# 20190314.net
KiCad netlist of a schematic drawn in EAGLE
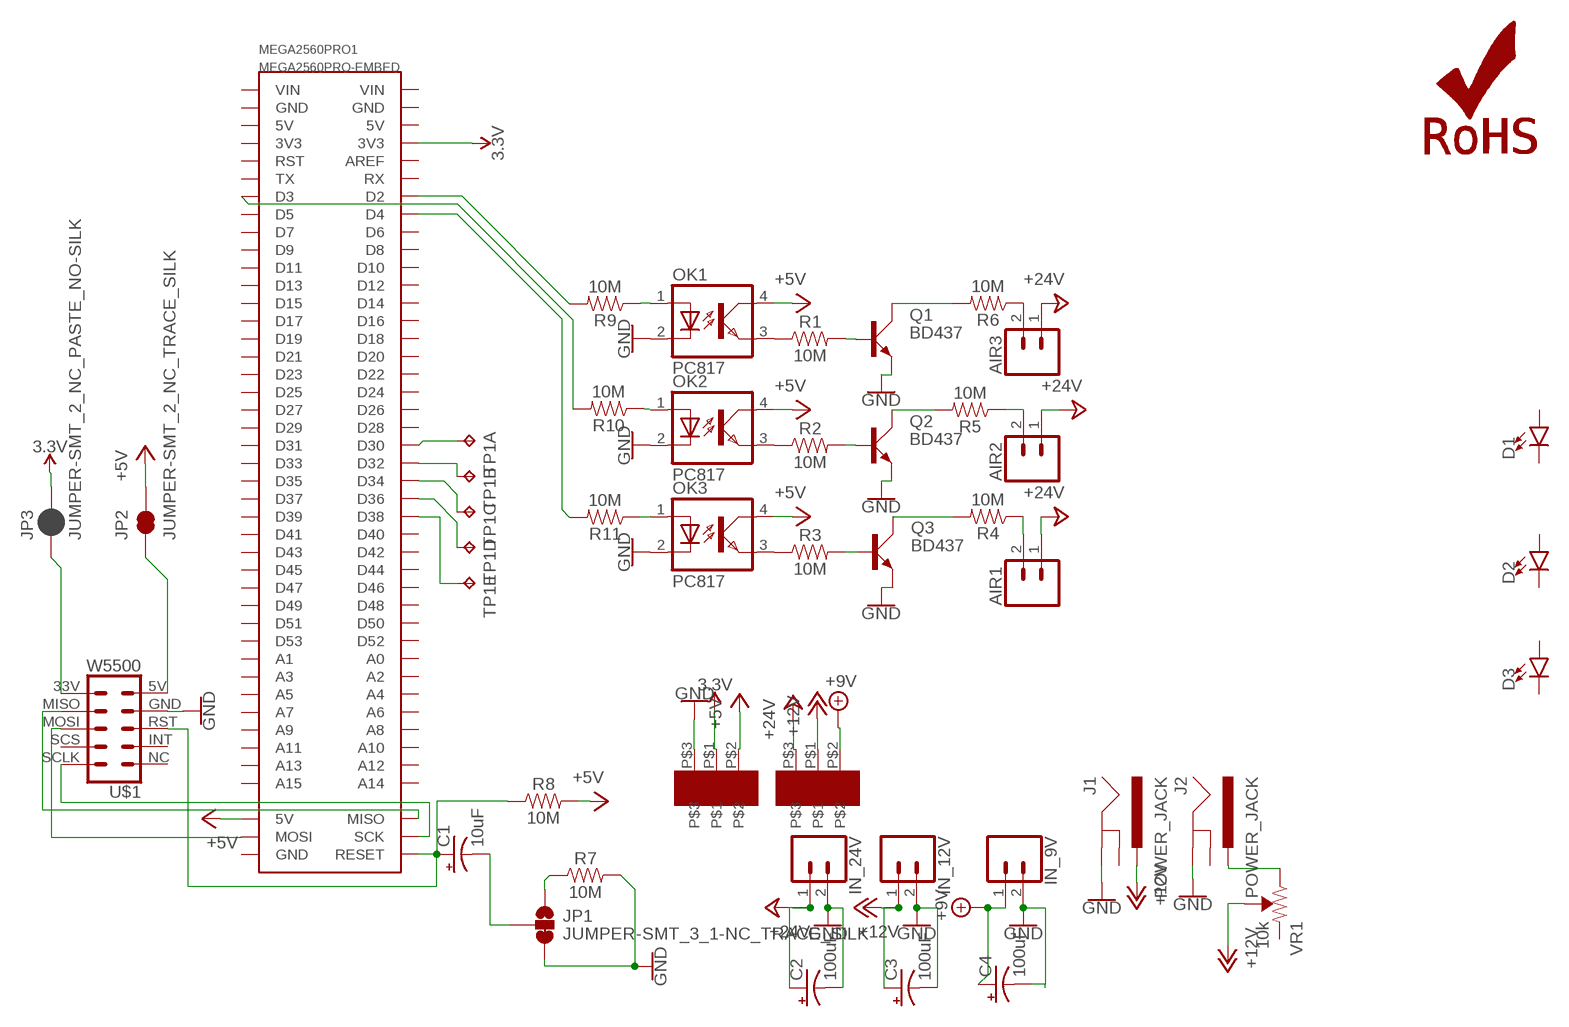
[diagram p0: schematic, sheet 1]

(export (version "E")
  (design (tool "Eeschema 10.0.6"))
  (components
    (comp (ref "AIR1")
      (value "CONN_02POLAR_LOCK")
      (footprint "eagle-import:MOLEX-1X2_LOCK")
      (libsource (lib "eagle-import") (part "CONN_02POLAR_LOCK"))
    )
    (comp (ref "AIR2")
      (value "CONN_02POLAR_LOCK")
      (footprint "eagle-import:MOLEX-1X2_LOCK")
      (libsource (lib "eagle-import") (part "CONN_02POLAR_LOCK"))
    )
    (comp (ref "AIR3")
      (value "CONN_02POLAR_LOCK")
      (footprint "eagle-import:MOLEX-1X2_LOCK")
      (libsource (lib "eagle-import") (part "CONN_02POLAR_LOCK"))
    )
    (comp (ref "C1")
      (value "10uF")
      (footprint "eagle-import:CPOL-RADIAL-2.5MM-5MM-KIT")
      (libsource (lib "eagle-import") (part "10UF-POLAR-RADIAL-2.5MM-KIT-25V-20%"))
    )
    (comp (ref "C2")
      (value "100uF")
      (footprint "eagle-import:CPOL-RADIAL-2.5MM-6.5MM")
      (libsource (lib "eagle-import") (part "100UF-POLAR-RADIAL-2.5MM-25V-20%"))
    )
    (comp (ref "C3")
      (value "100uF")
      (footprint "eagle-import:CPOL-RADIAL-2.5MM-6.5MM")
      (libsource (lib "eagle-import") (part "100UF-POLAR-RADIAL-2.5MM-25V-20%"))
    )
    (comp (ref "C4")
      (value "100uF")
      (footprint "eagle-import:CPOL-RADIAL-2.5MM-6.5MM")
      (libsource (lib "eagle-import") (part "100UF-POLAR-RADIAL-2.5MM-25V-20%"))
    )
    (comp (ref "D1")
      (value "LED5MM")
      (footprint "eagle-import:LED_5MM")
      (libsource (lib "eagle-import") (part "LED5MM"))
    )
    (comp (ref "D2")
      (value "LED5MM")
      (footprint "eagle-import:LED_5MM")
      (libsource (lib "eagle-import") (part "LED5MM"))
    )
    (comp (ref "D3")
      (value "LED5MM")
      (footprint "eagle-import:LED_5MM")
      (libsource (lib "eagle-import") (part "LED5MM"))
    )
    (comp (ref "IN_9V")
      (value "CONN_02POLAR_LOCK")
      (footprint "eagle-import:MOLEX-1X2_LOCK")
      (libsource (lib "eagle-import") (part "CONN_02POLAR_LOCK"))
    )
    (comp (ref "IN_12V")
      (value "CONN_02POLAR_LOCK")
      (footprint "eagle-import:MOLEX-1X2_LOCK")
      (libsource (lib "eagle-import") (part "CONN_02POLAR_LOCK"))
    )
    (comp (ref "IN_24V")
      (value "CONN_02POLAR_LOCK")
      (footprint "eagle-import:MOLEX-1X2_LOCK")
      (libsource (lib "eagle-import") (part "CONN_02POLAR_LOCK"))
    )
    (comp (ref "J1")
      (value "POWER_JACK")
      (footprint "eagle-import:POWER_JACK_PTH")
      (libsource (lib "eagle-import") (part "POWER_JACK"))
    )
    (comp (ref "J2")
      (value "POWER_JACK")
      (footprint "eagle-import:POWER_JACK_PTH")
      (libsource (lib "eagle-import") (part "POWER_JACK"))
    )
    (comp (ref "JP1")
      (value "JUMPER-SMT_3_1-NC_TRACE_SILK")
      (footprint "eagle-import:SMT-JUMPER_3_1-NC_TRACE_SILK")
      (libsource (lib "eagle-import") (part "JUMPER-SMT_3_1-NC_TRACE_SILK"))
    )
    (comp (ref "JP2")
      (value "JUMPER-SMT_2_NC_TRACE_SILK")
      (footprint "eagle-import:SMT-JUMPER_2_NC_TRACE_SILK")
      (libsource (lib "eagle-import") (part "JUMPER-SMT_2_NC_TRACE_SILK"))
    )
    (comp (ref "JP3")
      (value "JUMPER-SMT_2_NC_PASTE_NO-SILK")
      (footprint "eagle-import:SMT-JUMPER_2_NC_PASTE_NO-SILK")
      (libsource (lib "eagle-import") (part "JUMPER-SMT_2_NC_PASTE_NO-SILK"))
    )
    (comp (ref "LOGO1")
      (value "ROHS_LOGO")
      (footprint "eagle-import:ROHS_LOGO_0.18_IN")
      (libsource (lib "eagle-import") (part "ROHS_LOGO"))
    )
    (comp (ref "MEGA2560PRO1")
      (value "MEGA2560PRO-EMBED")
      (footprint "eagle-import:MEGA2560PRO-EMBED")
      (libsource (lib "eagle-import") (part "MEGA2560PRO-EMBED"))
    )
    (comp (ref "OK1")
      (value "PC817")
      (footprint "eagle-import:DIL04")
      (fields (field (name "MPN") "PC817X4J000F"))
      (libsource (lib "eagle-import") (part "PC817"))
    )
    (comp (ref "OK2")
      (value "PC817")
      (footprint "eagle-import:DIL04")
      (fields (field (name "MPN") "PC817X4J000F"))
      (libsource (lib "eagle-import") (part "PC817"))
    )
    (comp (ref "OK3")
      (value "PC817")
      (footprint "eagle-import:DIL04")
      (fields (field (name "MPN") "PC817X4J000F"))
      (libsource (lib "eagle-import") (part "PC817"))
    )
    (comp (ref "Q1")
      (value "BD437")
      (footprint "eagle-import:TO126AV")
      (libsource (lib "eagle-import") (part "BD437"))
    )
    (comp (ref "Q2")
      (value "BD437")
      (footprint "eagle-import:TO126AV")
      (libsource (lib "eagle-import") (part "BD437"))
    )
    (comp (ref "Q3")
      (value "BD437")
      (footprint "eagle-import:TO126AV")
      (libsource (lib "eagle-import") (part "BD437"))
    )
    (comp (ref "R1")
      (value "10M")
      (footprint "eagle-import:AXIAL-0.3")
      (libsource (lib "eagle-import") (part "10MOHM-HORIZ-1/4W-5%"))
    )
    (comp (ref "R2")
      (value "10M")
      (footprint "eagle-import:AXIAL-0.3")
      (libsource (lib "eagle-import") (part "10MOHM-HORIZ-1/4W-5%"))
    )
    (comp (ref "R3")
      (value "10M")
      (footprint "eagle-import:AXIAL-0.3")
      (libsource (lib "eagle-import") (part "10MOHM-HORIZ-1/4W-5%"))
    )
    (comp (ref "R4")
      (value "10M")
      (footprint "eagle-import:AXIAL-0.3")
      (libsource (lib "eagle-import") (part "10MOHM-HORIZ-1/4W-5%"))
    )
    (comp (ref "R5")
      (value "10M")
      (footprint "eagle-import:AXIAL-0.3")
      (libsource (lib "eagle-import") (part "10MOHM-HORIZ-1/4W-5%"))
    )
    (comp (ref "R6")
      (value "10M")
      (footprint "eagle-import:AXIAL-0.3")
      (libsource (lib "eagle-import") (part "10MOHM-HORIZ-1/4W-5%"))
    )
    (comp (ref "R7")
      (value "10M")
      (footprint "eagle-import:AXIAL-0.3")
      (libsource (lib "eagle-import") (part "10MOHM-HORIZ-1/4W-5%"))
    )
    (comp (ref "R8")
      (value "10M")
      (footprint "eagle-import:AXIAL-0.3")
      (libsource (lib "eagle-import") (part "10MOHM-HORIZ-1/4W-5%"))
    )
    (comp (ref "R9")
      (value "10M")
      (footprint "eagle-import:AXIAL-0.3")
      (libsource (lib "eagle-import") (part "10MOHM-HORIZ-1/4W-5%"))
    )
    (comp (ref "R10")
      (value "10M")
      (footprint "eagle-import:AXIAL-0.3")
      (libsource (lib "eagle-import") (part "10MOHM-HORIZ-1/4W-5%"))
    )
    (comp (ref "R11")
      (value "10M")
      (footprint "eagle-import:AXIAL-0.3")
      (libsource (lib "eagle-import") (part "10MOHM-HORIZ-1/4W-5%"))
    )
    (comp (ref "TP1")
      (value "TP5P5-25-13")
      (footprint "eagle-import:P5-25-13")
      (libsource (lib "eagle-import") (part "TP5P5-25-13"))
    )
    (comp (ref "U$1")
      (value "W5500")
      (footprint "eagle-import:W5500")
      (libsource (lib "eagle-import") (part "W5500"))
    )
    (comp (ref "U$3")
      (value "AC_3PIN")
      (footprint "eagle-import:AC3PIN15MM")
      (libsource (lib "eagle-import") (part "AC_3PIN"))
    )
    (comp (ref "U$4")
      (value "AC_3PIN")
      (footprint "eagle-import:AC3PIN15MM")
      (libsource (lib "eagle-import") (part "AC_3PIN"))
    )
    (comp (ref "VR1")
      (value "10k")
      (footprint "eagle-import:TRIMPOT-PTH-3386U")
      (libsource (lib "eagle-import") (part "TRIMPOT-PTH-10MM-KNOB-1/2W-10%"))
    )
  )
  (nets
    (net (code "1") (name "+5V") (class "Default")
      (node (ref "JP2") (pin "2") (pinfunction "2_2") (pintype "passive"))
      (node (ref "MEGA2560PRO1") (pin "5V@3") (pinfunction "5V_5V@3") (pintype "bidirectional"))
      (node (ref "OK1") (pin "4") (pinfunction "COL_4") (pintype "passive"))
      (node (ref "OK2") (pin "4") (pinfunction "COL_4") (pintype "passive"))
      (node (ref "OK3") (pin "4") (pinfunction "COL_4") (pintype "passive"))
      (node (ref "R8") (pin "P$2") (pinfunction "2_P$2") (pintype "passive"))
      (node (ref "U$4") (pin "P$2") (pinfunction "P$2_P$2") (pintype "bidirectional"))
    )
    (net (code "2") (name "+9V") (class "Default")
      (node (ref "C4") (pin "1") (pinfunction "+_1") (pintype "passive"))
      (node (ref "IN_9V") (pin "1") (pinfunction "1_1") (pintype "passive"))
      (node (ref "U$3") (pin "P$2") (pinfunction "P$2_P$2") (pintype "bidirectional"))
    )
    (net (code "3") (name "+12V") (class "Default")
      (node (ref "C3") (pin "1") (pinfunction "+_1") (pintype "passive"))
      (node (ref "IN_12V") (pin "1") (pinfunction "1_1") (pintype "passive"))
      (node (ref "J1") (pin "PWR") (pinfunction "PWR_PWR") (pintype "bidirectional"))
      (node (ref "U$3") (pin "P$1") (pinfunction "P$1_P$1") (pintype "bidirectional"))
      (node (ref "VR1") (pin "2") (pinfunction "WIPER_2") (pintype "passive"))
    )
    (net (code "4") (name "+24V") (class "Default")
      (node (ref "AIR1") (pin "1") (pinfunction "1_1") (pintype "passive"))
      (node (ref "AIR2") (pin "1") (pinfunction "1_1") (pintype "passive"))
      (node (ref "AIR3") (pin "1") (pinfunction "1_1") (pintype "passive"))
      (node (ref "C2") (pin "1") (pinfunction "+_1") (pintype "passive"))
      (node (ref "IN_24V") (pin "1") (pinfunction "1_1") (pintype "passive"))
      (node (ref "U$3") (pin "P$3") (pinfunction "P$3_P$3") (pintype "bidirectional"))
    )
    (net (code "5") (name "3.3V") (class "Default")
      (node (ref "JP3") (pin "2") (pinfunction "2_2") (pintype "passive"))
      (node (ref "MEGA2560PRO1") (pin "3V3@2") (pinfunction "3V3_3V3@2") (pintype "bidirectional"))
      (node (ref "U$4") (pin "P$1") (pinfunction "P$1_P$1") (pintype "bidirectional"))
    )
    (net (code "6") (name "GND") (class "Default")
      (node (ref "C2") (pin "2") (pinfunction "-_2") (pintype "passive"))
      (node (ref "C3") (pin "2") (pinfunction "-_2") (pintype "passive"))
      (node (ref "C4") (pin "2") (pinfunction "-_2") (pintype "passive"))
      (node (ref "IN_12V") (pin "2") (pinfunction "2_2") (pintype "passive"))
      (node (ref "IN_24V") (pin "2") (pinfunction "2_2") (pintype "passive"))
      (node (ref "IN_9V") (pin "2") (pinfunction "2_2") (pintype "passive"))
      (node (ref "J1") (pin "GND") (pinfunction "GND_GND") (pintype "bidirectional"))
      (node (ref "J2") (pin "GND") (pinfunction "GND_GND") (pintype "bidirectional"))
      (node (ref "JP1") (pin "3") (pinfunction "3_3") (pintype "passive"))
      (node (ref "OK1") (pin "2") (pinfunction "C_2") (pintype "passive"))
      (node (ref "OK2") (pin "2") (pinfunction "C_2") (pintype "passive"))
      (node (ref "OK3") (pin "2") (pinfunction "C_2") (pintype "passive"))
      (node (ref "Q1") (pin "E") (pinfunction "E_E") (pintype "passive"))
      (node (ref "Q2") (pin "E") (pinfunction "E_E") (pintype "passive"))
      (node (ref "Q3") (pin "E") (pinfunction "E_E") (pintype "passive"))
      (node (ref "R7") (pin "P$2") (pinfunction "2_P$2") (pintype "passive"))
      (node (ref "U$1") (pin "GND") (pinfunction "GND_GND") (pintype "passive"))
      (node (ref "U$4") (pin "P$3") (pinfunction "P$3_P$3") (pintype "bidirectional"))
    )
    (net (code "7") (name "Net-(C1-+)") (class "Default")
      (node (ref "C1") (pin "1") (pinfunction "+_1") (pintype "passive"))
      (node (ref "MEGA2560PRO1") (pin "RESET") (pinfunction "RESET_RESET") (pintype "bidirectional"))
      (node (ref "R8") (pin "P$1") (pinfunction "1_P$1") (pintype "passive"))
      (node (ref "U$1") (pin "RST") (pinfunction "RST_RST") (pintype "passive"))
    )
    (net (code "8") (name "Net-(C1--)") (class "Default")
      (node (ref "C1") (pin "2") (pinfunction "-_2") (pintype "passive"))
      (node (ref "JP1") (pin "2") (pinfunction "2_2") (pintype "passive"))
    )
    (net (code "9") (name "Net-(JP2-Pad1)") (class "Default")
      (node (ref "JP2") (pin "1") (pinfunction "1_1") (pintype "passive"))
      (node (ref "U$1") (pin "5V") (pinfunction "5V_5V") (pintype "passive"))
    )
    (net (code "10") (name "Net-(MEGA2560PRO1-PadMISO)") (class "Default")
      (node (ref "MEGA2560PRO1") (pin "MISO") (pinfunction "MISO_MISO") (pintype "bidirectional"))
      (node (ref "U$1") (pin "MISO") (pinfunction "MISO_MISO") (pintype "passive"))
    )
    (net (code "11") (name "Net-(MEGA2560PRO1-PadMOSI)") (class "Default")
      (node (ref "MEGA2560PRO1") (pin "MOSI") (pinfunction "MOSI_MOSI") (pintype "bidirectional"))
      (node (ref "U$1") (pin "MOSI") (pinfunction "MOSI_MOSI") (pintype "passive"))
    )
    (net (code "12") (name "Net-(MEGA2560PRO1-PadSCK)") (class "Default")
      (node (ref "MEGA2560PRO1") (pin "SCK") (pinfunction "SCK_SCK") (pintype "bidirectional"))
      (node (ref "U$1") (pin "SCLK") (pinfunction "SCLK_SCLK") (pintype "passive"))
    )
    (net (code "13") (name "Net-(OK1-A)") (class "Default")
      (node (ref "OK1") (pin "1") (pinfunction "A_1") (pintype "passive"))
      (node (ref "R9") (pin "P$1") (pinfunction "1_P$1") (pintype "passive"))
    )
    (net (code "14") (name "Net-(OK1-EMIT)") (class "Default")
      (node (ref "OK1") (pin "3") (pinfunction "EMIT_3") (pintype "passive"))
      (node (ref "R1") (pin "P$1") (pinfunction "1_P$1") (pintype "passive"))
    )
    (net (code "15") (name "Net-(OK2-A)") (class "Default")
      (node (ref "OK2") (pin "1") (pinfunction "A_1") (pintype "passive"))
      (node (ref "R10") (pin "P$1") (pinfunction "1_P$1") (pintype "passive"))
    )
    (net (code "16") (name "Net-(OK2-EMIT)") (class "Default")
      (node (ref "OK2") (pin "3") (pinfunction "EMIT_3") (pintype "passive"))
      (node (ref "R2") (pin "P$1") (pinfunction "1_P$1") (pintype "passive"))
    )
    (net (code "17") (name "Net-(OK3-A)") (class "Default")
      (node (ref "OK3") (pin "1") (pinfunction "A_1") (pintype "passive"))
      (node (ref "R11") (pin "P$1") (pinfunction "1_P$1") (pintype "passive"))
    )
    (net (code "18") (name "Net-(OK3-EMIT)") (class "Default")
      (node (ref "OK3") (pin "3") (pinfunction "EMIT_3") (pintype "passive"))
      (node (ref "R3") (pin "P$1") (pinfunction "1_P$1") (pintype "passive"))
    )
    (net (code "19") (name "Net-(R1-2)") (class "Default")
      (node (ref "Q1") (pin "B") (pinfunction "B_B") (pintype "passive"))
      (node (ref "R1") (pin "P$2") (pinfunction "2_P$2") (pintype "passive"))
    )
    (net (code "20") (name "Net-(R2-2)") (class "Default")
      (node (ref "Q2") (pin "B") (pinfunction "B_B") (pintype "passive"))
      (node (ref "R2") (pin "P$2") (pinfunction "2_P$2") (pintype "passive"))
    )
    (net (code "21") (name "Net-(R3-2)") (class "Default")
      (node (ref "Q3") (pin "B") (pinfunction "B_B") (pintype "passive"))
      (node (ref "R3") (pin "P$2") (pinfunction "2_P$2") (pintype "passive"))
    )
    (net (code "22") (name "Net-(R4-1)") (class "Default")
      (node (ref "AIR1") (pin "2") (pinfunction "2_2") (pintype "passive"))
      (node (ref "R4") (pin "P$1") (pinfunction "1_P$1") (pintype "passive"))
    )
    (net (code "23") (name "Net-(R4-2)") (class "Default")
      (node (ref "Q3") (pin "C") (pinfunction "C_C") (pintype "passive"))
      (node (ref "R4") (pin "P$2") (pinfunction "2_P$2") (pintype "passive"))
    )
    (net (code "24") (name "Net-(R5-1)") (class "Default")
      (node (ref "AIR2") (pin "2") (pinfunction "2_2") (pintype "passive"))
      (node (ref "R5") (pin "P$1") (pinfunction "1_P$1") (pintype "passive"))
    )
    (net (code "25") (name "Net-(R5-2)") (class "Default")
      (node (ref "Q2") (pin "C") (pinfunction "C_C") (pintype "passive"))
      (node (ref "R5") (pin "P$2") (pinfunction "2_P$2") (pintype "passive"))
    )
    (net (code "26") (name "Net-(R6-1)") (class "Default")
      (node (ref "AIR3") (pin "2") (pinfunction "2_2") (pintype "passive"))
      (node (ref "R6") (pin "P$1") (pinfunction "1_P$1") (pintype "passive"))
    )
    (net (code "27") (name "Net-(R6-2)") (class "Default")
      (node (ref "Q1") (pin "C") (pinfunction "C_C") (pintype "passive"))
      (node (ref "R6") (pin "P$2") (pinfunction "2_P$2") (pintype "passive"))
    )
    (net (code "28") (name "Net-(R7-1)") (class "Default")
      (node (ref "JP1") (pin "1") (pinfunction "1_1") (pintype "passive"))
      (node (ref "R7") (pin "P$1") (pinfunction "1_P$1") (pintype "passive"))
    )
    (net (code "29") (name "Net-(R9-2)") (class "Default")
      (node (ref "MEGA2560PRO1") (pin "D2") (pinfunction "D2_D2") (pintype "bidirectional"))
      (node (ref "R9") (pin "P$2") (pinfunction "2_P$2") (pintype "passive"))
    )
    (net (code "30") (name "Net-(R10-2)") (class "Default")
      (node (ref "MEGA2560PRO1") (pin "D3") (pinfunction "D3_D3") (pintype "bidirectional"))
      (node (ref "R10") (pin "P$2") (pinfunction "2_P$2") (pintype "passive"))
    )
    (net (code "31") (name "Net-(R11-2)") (class "Default")
      (node (ref "MEGA2560PRO1") (pin "D4") (pinfunction "D4_D4") (pintype "bidirectional"))
      (node (ref "R11") (pin "P$2") (pinfunction "2_P$2") (pintype "passive"))
    )
    (net (code "32") (name "Net-(TP1A-TP)") (class "Default")
      (node (ref "MEGA2560PRO1") (pin "D30") (pinfunction "D30_D30") (pintype "bidirectional"))
      (node (ref "TP1") (pin "TP-1") (pinfunction "TP_TP-1") (pintype "input"))
    )
    (net (code "33") (name "Net-(TP1B-TP)") (class "Default")
      (node (ref "MEGA2560PRO1") (pin "D32") (pinfunction "D32_D32") (pintype "bidirectional"))
      (node (ref "TP1") (pin "TP-2") (pinfunction "TP_TP-2") (pintype "input"))
    )
    (net (code "34") (name "Net-(TP1C-TP)") (class "Default")
      (node (ref "MEGA2560PRO1") (pin "D34") (pinfunction "D34_D34") (pintype "bidirectional"))
      (node (ref "TP1") (pin "TP-3") (pinfunction "TP_TP-3") (pintype "input"))
    )
    (net (code "35") (name "Net-(TP1D-TP)") (class "Default")
      (node (ref "MEGA2560PRO1") (pin "D36") (pinfunction "D36_D36") (pintype "bidirectional"))
      (node (ref "TP1") (pin "TP-4") (pinfunction "TP_TP-4") (pintype "input"))
    )
    (net (code "36") (name "Net-(TP1E-TP)") (class "Default")
      (node (ref "MEGA2560PRO1") (pin "D38") (pinfunction "D38_D38") (pintype "bidirectional"))
      (node (ref "TP1") (pin "TP-5") (pinfunction "TP_TP-5") (pintype "input"))
    )
    (net (code "37") (name "Net-(U$1-3V3)") (class "Default")
      (node (ref "JP3") (pin "1") (pinfunction "1_1") (pintype "passive"))
      (node (ref "U$1") (pin "33V") (pinfunction "3V3_33V") (pintype "passive"))
    )
    (net (code "38") (name "Net-(VR1-CW)") (class "Default")
      (node (ref "J2") (pin "PWR") (pinfunction "PWR_PWR") (pintype "bidirectional"))
      (node (ref "VR1") (pin "3") (pinfunction "CW_3") (pintype "passive"))
    )
    (net (code "39") (name "unconnected-(D1-C-PadK)") (class "Default")
      (node (ref "D1") (pin "K") (pinfunction "C_K") (pintype "passive"))
    )
    (net (code "40") (name "unconnected-(D1-PadA)") (class "Default")
      (node (ref "D1") (pin "A") (pinfunction "A_A") (pintype "passive"))
    )
    (net (code "41") (name "unconnected-(D2-C-PadK)") (class "Default")
      (node (ref "D2") (pin "K") (pinfunction "C_K") (pintype "passive"))
    )
    (net (code "42") (name "unconnected-(D2-PadA)") (class "Default")
      (node (ref "D2") (pin "A") (pinfunction "A_A") (pintype "passive"))
    )
    (net (code "43") (name "unconnected-(D3-C-PadK)") (class "Default")
      (node (ref "D3") (pin "K") (pinfunction "C_K") (pintype "passive"))
    )
    (net (code "44") (name "unconnected-(D3-PadA)") (class "Default")
      (node (ref "D3") (pin "A") (pinfunction "A_A") (pintype "passive"))
    )
    (net (code "45") (name "unconnected-(J1-PadGNDBREAK)") (class "Default")
      (node (ref "J1") (pin "GNDBREAK") (pinfunction "GNDBREAK_GNDBREAK") (pintype "bidirectional"))
    )
    (net (code "46") (name "unconnected-(J2-PadGNDBREAK)") (class "Default")
      (node (ref "J2") (pin "GNDBREAK") (pinfunction "GNDBREAK_GNDBREAK") (pintype "bidirectional"))
    )
    (net (code "47") (name "unconnected-(MEGA2560PRO1-3V3-Pad3V3@1)") (class "Default")
      (node (ref "MEGA2560PRO1") (pin "3V3@1") (pinfunction "3V3_3V3@1") (pintype "bidirectional"))
    )
    (net (code "48") (name "unconnected-(MEGA2560PRO1-5V-Pad5V@1)") (class "Default")
      (node (ref "MEGA2560PRO1") (pin "5V@1") (pinfunction "5V_5V@1") (pintype "bidirectional"))
    )
    (net (code "49") (name "unconnected-(MEGA2560PRO1-5V-Pad5V@2)") (class "Default")
      (node (ref "MEGA2560PRO1") (pin "5V@2") (pinfunction "5V_5V@2") (pintype "bidirectional"))
    )
    (net (code "50") (name "unconnected-(MEGA2560PRO1-GND-PadGND@1)") (class "Default")
      (node (ref "MEGA2560PRO1") (pin "GND@1") (pinfunction "GND_GND@1") (pintype "bidirectional"))
    )
    (net (code "51") (name "unconnected-(MEGA2560PRO1-GND-PadGND@2)") (class "Default")
      (node (ref "MEGA2560PRO1") (pin "GND@2") (pinfunction "GND_GND@2") (pintype "bidirectional"))
    )
    (net (code "52") (name "unconnected-(MEGA2560PRO1-GND-PadGND@3)") (class "Default")
      (node (ref "MEGA2560PRO1") (pin "GND@3") (pinfunction "GND_GND@3") (pintype "bidirectional"))
    )
    (net (code "53") (name "unconnected-(MEGA2560PRO1-PadA0)") (class "Default")
      (node (ref "MEGA2560PRO1") (pin "A0") (pinfunction "A0_A0") (pintype "bidirectional"))
    )
    (net (code "54") (name "unconnected-(MEGA2560PRO1-PadA1)") (class "Default")
      (node (ref "MEGA2560PRO1") (pin "A1") (pinfunction "A1_A1") (pintype "bidirectional"))
    )
    (net (code "55") (name "unconnected-(MEGA2560PRO1-PadA2)") (class "Default")
      (node (ref "MEGA2560PRO1") (pin "A2") (pinfunction "A2_A2") (pintype "bidirectional"))
    )
    (net (code "56") (name "unconnected-(MEGA2560PRO1-PadA3)") (class "Default")
      (node (ref "MEGA2560PRO1") (pin "A3") (pinfunction "A3_A3") (pintype "bidirectional"))
    )
    (net (code "57") (name "unconnected-(MEGA2560PRO1-PadA4)") (class "Default")
      (node (ref "MEGA2560PRO1") (pin "A4") (pinfunction "A4_A4") (pintype "bidirectional"))
    )
    (net (code "58") (name "unconnected-(MEGA2560PRO1-PadA5)") (class "Default")
      (node (ref "MEGA2560PRO1") (pin "A5") (pinfunction "A5_A5") (pintype "bidirectional"))
    )
    (net (code "59") (name "unconnected-(MEGA2560PRO1-PadA6)") (class "Default")
      (node (ref "MEGA2560PRO1") (pin "A6") (pinfunction "A6_A6") (pintype "bidirectional"))
    )
    (net (code "60") (name "unconnected-(MEGA2560PRO1-PadA7)") (class "Default")
      (node (ref "MEGA2560PRO1") (pin "A7") (pinfunction "A7_A7") (pintype "bidirectional"))
    )
    (net (code "61") (name "unconnected-(MEGA2560PRO1-PadA8)") (class "Default")
      (node (ref "MEGA2560PRO1") (pin "A8") (pinfunction "A8_A8") (pintype "bidirectional"))
    )
    (net (code "62") (name "unconnected-(MEGA2560PRO1-PadA9)") (class "Default")
      (node (ref "MEGA2560PRO1") (pin "A9") (pinfunction "A9_A9") (pintype "bidirectional"))
    )
    (net (code "63") (name "unconnected-(MEGA2560PRO1-PadA10)") (class "Default")
      (node (ref "MEGA2560PRO1") (pin "A10") (pinfunction "A10_A10") (pintype "bidirectional"))
    )
    (net (code "64") (name "unconnected-(MEGA2560PRO1-PadA11)") (class "Default")
      (node (ref "MEGA2560PRO1") (pin "A11") (pinfunction "A11_A11") (pintype "bidirectional"))
    )
    (net (code "65") (name "unconnected-(MEGA2560PRO1-PadA12)") (class "Default")
      (node (ref "MEGA2560PRO1") (pin "A12") (pinfunction "A12_A12") (pintype "bidirectional"))
    )
    (net (code "66") (name "unconnected-(MEGA2560PRO1-PadA13)") (class "Default")
      (node (ref "MEGA2560PRO1") (pin "A13") (pinfunction "A13_A13") (pintype "bidirectional"))
    )
    (net (code "67") (name "unconnected-(MEGA2560PRO1-PadA14)") (class "Default")
      (node (ref "MEGA2560PRO1") (pin "A14") (pinfunction "A14_A14") (pintype "bidirectional"))
    )
    (net (code "68") (name "unconnected-(MEGA2560PRO1-PadA15)") (class "Default")
      (node (ref "MEGA2560PRO1") (pin "A15") (pinfunction "A15_A15") (pintype "bidirectional"))
    )
    (net (code "69") (name "unconnected-(MEGA2560PRO1-PadAREF)") (class "Default")
      (node (ref "MEGA2560PRO1") (pin "AREF") (pinfunction "AREF_AREF") (pintype "bidirectional"))
    )
    (net (code "70") (name "unconnected-(MEGA2560PRO1-PadD5)") (class "Default")
      (node (ref "MEGA2560PRO1") (pin "D5") (pinfunction "D5_D5") (pintype "bidirectional"))
    )
    (net (code "71") (name "unconnected-(MEGA2560PRO1-PadD6)") (class "Default")
      (node (ref "MEGA2560PRO1") (pin "D6") (pinfunction "D6_D6") (pintype "bidirectional"))
    )
    (net (code "72") (name "unconnected-(MEGA2560PRO1-PadD7)") (class "Default")
      (node (ref "MEGA2560PRO1") (pin "D7") (pinfunction "D7_D7") (pintype "bidirectional"))
    )
    (net (code "73") (name "unconnected-(MEGA2560PRO1-PadD8)") (class "Default")
      (node (ref "MEGA2560PRO1") (pin "D8") (pinfunction "D8_D8") (pintype "bidirectional"))
    )
    (net (code "74") (name "unconnected-(MEGA2560PRO1-PadD9)") (class "Default")
      (node (ref "MEGA2560PRO1") (pin "D9") (pinfunction "D9_D9") (pintype "bidirectional"))
    )
    (net (code "75") (name "unconnected-(MEGA2560PRO1-PadD10)") (class "Default")
      (node (ref "MEGA2560PRO1") (pin "D10") (pinfunction "D10_D10") (pintype "bidirectional"))
    )
    (net (code "76") (name "unconnected-(MEGA2560PRO1-PadD11)") (class "Default")
      (node (ref "MEGA2560PRO1") (pin "D11") (pinfunction "D11_D11") (pintype "bidirectional"))
    )
    (net (code "77") (name "unconnected-(MEGA2560PRO1-PadD12)") (class "Default")
      (node (ref "MEGA2560PRO1") (pin "D12") (pinfunction "D12_D12") (pintype "bidirectional"))
    )
    (net (code "78") (name "unconnected-(MEGA2560PRO1-PadD13)") (class "Default")
      (node (ref "MEGA2560PRO1") (pin "D13") (pinfunction "D13_D13") (pintype "bidirectional"))
    )
    (net (code "79") (name "unconnected-(MEGA2560PRO1-PadD14)") (class "Default")
      (node (ref "MEGA2560PRO1") (pin "D14") (pinfunction "D14_D14") (pintype "bidirectional"))
    )
    (net (code "80") (name "unconnected-(MEGA2560PRO1-PadD15)") (class "Default")
      (node (ref "MEGA2560PRO1") (pin "D15") (pinfunction "D15_D15") (pintype "bidirectional"))
    )
    (net (code "81") (name "unconnected-(MEGA2560PRO1-PadD16)") (class "Default")
      (node (ref "MEGA2560PRO1") (pin "D16") (pinfunction "D16_D16") (pintype "bidirectional"))
    )
    (net (code "82") (name "unconnected-(MEGA2560PRO1-PadD17)") (class "Default")
      (node (ref "MEGA2560PRO1") (pin "D17") (pinfunction "D17_D17") (pintype "bidirectional"))
    )
    (net (code "83") (name "unconnected-(MEGA2560PRO1-PadD18)") (class "Default")
      (node (ref "MEGA2560PRO1") (pin "D18") (pinfunction "D18_D18") (pintype "bidirectional"))
    )
    (net (code "84") (name "unconnected-(MEGA2560PRO1-PadD19)") (class "Default")
      (node (ref "MEGA2560PRO1") (pin "D19") (pinfunction "D19_D19") (pintype "bidirectional"))
    )
    (net (code "85") (name "unconnected-(MEGA2560PRO1-PadD20)") (class "Default")
      (node (ref "MEGA2560PRO1") (pin "D20") (pinfunction "D20_D20") (pintype "bidirectional"))
    )
    (net (code "86") (name "unconnected-(MEGA2560PRO1-PadD21)") (class "Default")
      (node (ref "MEGA2560PRO1") (pin "D21") (pinfunction "D21_D21") (pintype "bidirectional"))
    )
    (net (code "87") (name "unconnected-(MEGA2560PRO1-PadD22)") (class "Default")
      (node (ref "MEGA2560PRO1") (pin "D22") (pinfunction "D22_D22") (pintype "bidirectional"))
    )
    (net (code "88") (name "unconnected-(MEGA2560PRO1-PadD23)") (class "Default")
      (node (ref "MEGA2560PRO1") (pin "D23") (pinfunction "D23_D23") (pintype "bidirectional"))
    )
    (net (code "89") (name "unconnected-(MEGA2560PRO1-PadD24)") (class "Default")
      (node (ref "MEGA2560PRO1") (pin "D24") (pinfunction "D24_D24") (pintype "bidirectional"))
    )
    (net (code "90") (name "unconnected-(MEGA2560PRO1-PadD25)") (class "Default")
      (node (ref "MEGA2560PRO1") (pin "D25") (pinfunction "D25_D25") (pintype "bidirectional"))
    )
    (net (code "91") (name "unconnected-(MEGA2560PRO1-PadD26)") (class "Default")
      (node (ref "MEGA2560PRO1") (pin "D26") (pinfunction "D26_D26") (pintype "bidirectional"))
    )
    (net (code "92") (name "unconnected-(MEGA2560PRO1-PadD27)") (class "Default")
      (node (ref "MEGA2560PRO1") (pin "D27") (pinfunction "D27_D27") (pintype "bidirectional"))
    )
    (net (code "93") (name "unconnected-(MEGA2560PRO1-PadD28)") (class "Default")
      (node (ref "MEGA2560PRO1") (pin "D28") (pinfunction "D28_D28") (pintype "bidirectional"))
    )
    (net (code "94") (name "unconnected-(MEGA2560PRO1-PadD29)") (class "Default")
      (node (ref "MEGA2560PRO1") (pin "D29") (pinfunction "D29_D29") (pintype "bidirectional"))
    )
    (net (code "95") (name "unconnected-(MEGA2560PRO1-PadD31)") (class "Default")
      (node (ref "MEGA2560PRO1") (pin "D31") (pinfunction "D31_D31") (pintype "bidirectional"))
    )
    (net (code "96") (name "unconnected-(MEGA2560PRO1-PadD33)") (class "Default")
      (node (ref "MEGA2560PRO1") (pin "D33") (pinfunction "D33_D33") (pintype "bidirectional"))
    )
    (net (code "97") (name "unconnected-(MEGA2560PRO1-PadD35)") (class "Default")
      (node (ref "MEGA2560PRO1") (pin "D35") (pinfunction "D35_D35") (pintype "bidirectional"))
    )
    (net (code "98") (name "unconnected-(MEGA2560PRO1-PadD37)") (class "Default")
      (node (ref "MEGA2560PRO1") (pin "D37") (pinfunction "D37_D37") (pintype "bidirectional"))
    )
    (net (code "99") (name "unconnected-(MEGA2560PRO1-PadD39)") (class "Default")
      (node (ref "MEGA2560PRO1") (pin "D39") (pinfunction "D39_D39") (pintype "bidirectional"))
    )
    (net (code "100") (name "unconnected-(MEGA2560PRO1-PadD40)") (class "Default")
      (node (ref "MEGA2560PRO1") (pin "D40") (pinfunction "D40_D40") (pintype "bidirectional"))
    )
    (net (code "101") (name "unconnected-(MEGA2560PRO1-PadD41)") (class "Default")
      (node (ref "MEGA2560PRO1") (pin "D41") (pinfunction "D41_D41") (pintype "bidirectional"))
    )
    (net (code "102") (name "unconnected-(MEGA2560PRO1-PadD42)") (class "Default")
      (node (ref "MEGA2560PRO1") (pin "D42") (pinfunction "D42_D42") (pintype "bidirectional"))
    )
    (net (code "103") (name "unconnected-(MEGA2560PRO1-PadD43)") (class "Default")
      (node (ref "MEGA2560PRO1") (pin "D43") (pinfunction "D43_D43") (pintype "bidirectional"))
    )
    (net (code "104") (name "unconnected-(MEGA2560PRO1-PadD44)") (class "Default")
      (node (ref "MEGA2560PRO1") (pin "D44") (pinfunction "D44_D44") (pintype "bidirectional"))
    )
    (net (code "105") (name "unconnected-(MEGA2560PRO1-PadD45)") (class "Default")
      (node (ref "MEGA2560PRO1") (pin "D45") (pinfunction "D45_D45") (pintype "bidirectional"))
    )
    (net (code "106") (name "unconnected-(MEGA2560PRO1-PadD46)") (class "Default")
      (node (ref "MEGA2560PRO1") (pin "D46") (pinfunction "D46_D46") (pintype "bidirectional"))
    )
    (net (code "107") (name "unconnected-(MEGA2560PRO1-PadD47)") (class "Default")
      (node (ref "MEGA2560PRO1") (pin "D47") (pinfunction "D47_D47") (pintype "bidirectional"))
    )
    (net (code "108") (name "unconnected-(MEGA2560PRO1-PadD48)") (class "Default")
      (node (ref "MEGA2560PRO1") (pin "D48") (pinfunction "D48_D48") (pintype "bidirectional"))
    )
    (net (code "109") (name "unconnected-(MEGA2560PRO1-PadD49)") (class "Default")
      (node (ref "MEGA2560PRO1") (pin "D49") (pinfunction "D49_D49") (pintype "bidirectional"))
    )
    (net (code "110") (name "unconnected-(MEGA2560PRO1-PadD50)") (class "Default")
      (node (ref "MEGA2560PRO1") (pin "D50") (pinfunction "D50_D50") (pintype "bidirectional"))
    )
    (net (code "111") (name "unconnected-(MEGA2560PRO1-PadD51)") (class "Default")
      (node (ref "MEGA2560PRO1") (pin "D51") (pinfunction "D51_D51") (pintype "bidirectional"))
    )
    (net (code "112") (name "unconnected-(MEGA2560PRO1-PadD52)") (class "Default")
      (node (ref "MEGA2560PRO1") (pin "D52") (pinfunction "D52_D52") (pintype "bidirectional"))
    )
    (net (code "113") (name "unconnected-(MEGA2560PRO1-PadD53)") (class "Default")
      (node (ref "MEGA2560PRO1") (pin "D53") (pinfunction "D53_D53") (pintype "bidirectional"))
    )
    (net (code "114") (name "unconnected-(MEGA2560PRO1-PadRST)") (class "Default")
      (node (ref "MEGA2560PRO1") (pin "RST") (pinfunction "RST_RST") (pintype "bidirectional"))
    )
    (net (code "115") (name "unconnected-(MEGA2560PRO1-PadRX)") (class "Default")
      (node (ref "MEGA2560PRO1") (pin "RX") (pinfunction "RX_RX") (pintype "bidirectional"))
    )
    (net (code "116") (name "unconnected-(MEGA2560PRO1-PadTX)") (class "Default")
      (node (ref "MEGA2560PRO1") (pin "TX") (pinfunction "TX_TX") (pintype "bidirectional"))
    )
    (net (code "117") (name "unconnected-(MEGA2560PRO1-VIN-PadVIN@1)") (class "Default")
      (node (ref "MEGA2560PRO1") (pin "VIN@1") (pinfunction "VIN_VIN@1") (pintype "bidirectional"))
    )
    (net (code "118") (name "unconnected-(MEGA2560PRO1-VIN-PadVIN@2)") (class "Default")
      (node (ref "MEGA2560PRO1") (pin "VIN@2") (pinfunction "VIN_VIN@2") (pintype "bidirectional"))
    )
    (net (code "119") (name "unconnected-(U$1-PadINT)") (class "Default")
      (node (ref "U$1") (pin "INT") (pinfunction "INT_INT") (pintype "passive"))
    )
    (net (code "120") (name "unconnected-(U$1-PadNC)") (class "Default")
      (node (ref "U$1") (pin "NC") (pinfunction "NC_NC") (pintype "passive"))
    )
    (net (code "121") (name "unconnected-(U$1-PadSCS)") (class "Default")
      (node (ref "U$1") (pin "SCS") (pinfunction "SCS_SCS") (pintype "passive"))
    )
    (net (code "122") (name "unconnected-(VR1-CCW-Pad1)") (class "Default")
      (node (ref "VR1") (pin "1") (pinfunction "CCW_1") (pintype "passive"))
    )
  )
)
